# DRV8323.net
KiCad netlist of a schematic drawn in Altium Designer
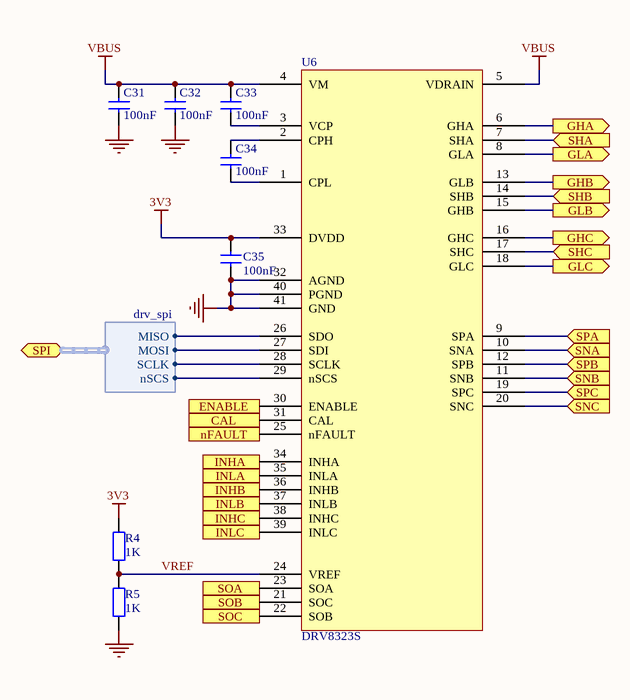
[diagram p0: DRV8323.SchDoc]

(export (version "E")
  (design (tool "Eeschema 10.0.6"))
  (components
    (comp (ref "C31")
      (value "100nF")
      (footprint "CAP0402(1005)_N")
      (description "Capacitor")
      (fields (field (name "PART") "cap_generic"))
      (libsource (lib "hitiqlib") (part "cap"))
    )
    (comp (ref "C32")
      (value "100nF")
      (footprint "CAP0402(1005)_N")
      (description "Capacitor")
      (fields (field (name "PART") "cap_generic"))
      (libsource (lib "hitiqlib") (part "cap"))
    )
    (comp (ref "C33")
      (value "100nF")
      (footprint "CAP0402(1005)_N")
      (description "Capacitor")
      (fields (field (name "PART") "cap_generic"))
      (libsource (lib "hitiqlib") (part "cap"))
    )
    (comp (ref "C34")
      (value "100nF")
      (footprint "CAP0402(1005)_N")
      (description "Capacitor")
      (fields (field (name "PART") "cap_generic"))
      (libsource (lib "hitiqlib") (part "cap"))
    )
    (comp (ref "C35")
      (value "100nF")
      (footprint "CAP0402(1005)_N")
      (description "Capacitor")
      (fields (field (name "PART") "cap_generic"))
      (libsource (lib "hitiqlib") (part "cap"))
    )
    (comp (ref "R4")
      (value "1K")
      (footprint "RESC0402(1005)_N")
      (description "Resistor")
      (fields (field (name "PART") "res_generic"))
      (libsource (lib "hitiqlib") (part "Resistor"))
    )
    (comp (ref "R5")
      (value "1K")
      (footprint "RESC0402(1005)_N")
      (description "Resistor")
      (fields (field (name "PART") "res_generic"))
      (libsource (lib "hitiqlib") (part "Resistor"))
    )
    (comp (ref "U6")
      (value "DRV8323S")
      (footprint "WQFN-40")
      (fields (field (name "MANUFACTURER") "Texas Instruments"))
      (libsource (lib "hitiqlib") (part "DRV8323S"))
    )
  )
  (nets
    (net (code "2") (name "/CAL") (class "Default")
      (node (ref "U6") (pin "31") (pinfunction "CAL_31") (pintype "passive"))
    )
    (net (code "3") (name "/ENABLE") (class "Default")
      (node (ref "U6") (pin "30") (pinfunction "ENABLE_30") (pintype "passive"))
    )
    (net (code "4") (name "/GHA") (class "Default")
      (node (ref "U6") (pin "6") (pinfunction "GHA_6") (pintype "passive"))
    )
    (net (code "5") (name "/GHB") (class "Default")
      (node (ref "U6") (pin "13") (pinfunction "GLB_13") (pintype "passive"))
    )
    (net (code "6") (name "/GHC") (class "Default")
      (node (ref "U6") (pin "16") (pinfunction "GHC_16") (pintype "passive"))
    )
    (net (code "7") (name "/GLA") (class "Default")
      (node (ref "U6") (pin "8") (pinfunction "GLA_8") (pintype "passive"))
    )
    (net (code "8") (name "/GLB") (class "Default")
      (node (ref "U6") (pin "15") (pinfunction "GHB_15") (pintype "passive"))
    )
    (net (code "9") (name "/GLC") (class "Default")
      (node (ref "U6") (pin "18") (pinfunction "GLC_18") (pintype "passive"))
    )
    (net (code "10") (name "/INHA") (class "Default")
      (node (ref "U6") (pin "34") (pinfunction "INHA_34") (pintype "passive"))
    )
    (net (code "11") (name "/INHB") (class "Default")
      (node (ref "U6") (pin "36") (pinfunction "INHB_36") (pintype "passive"))
    )
    (net (code "12") (name "/INHC") (class "Default")
      (node (ref "U6") (pin "38") (pinfunction "INHC_38") (pintype "passive"))
    )
    (net (code "13") (name "/INLA") (class "Default")
      (node (ref "U6") (pin "35") (pinfunction "INLA_35") (pintype "passive"))
    )
    (net (code "14") (name "/INLB") (class "Default")
      (node (ref "U6") (pin "37") (pinfunction "INLB_37") (pintype "passive"))
    )
    (net (code "15") (name "/INLC") (class "Default")
      (node (ref "U6") (pin "39") (pinfunction "INLC_39") (pintype "passive"))
    )
    (net (code "16") (name "/MISO") (class "Default")
      (node (ref "U6") (pin "26") (pinfunction "SDO_26") (pintype "passive"))
    )
    (net (code "17") (name "/MOSI") (class "Default")
      (node (ref "U6") (pin "27") (pinfunction "SDI_27") (pintype "passive"))
    )
    (net (code "18") (name "/SCLK") (class "Default")
      (node (ref "U6") (pin "28") (pinfunction "SCLK_28") (pintype "passive"))
    )
    (net (code "19") (name "/SHA") (class "Default")
      (node (ref "U6") (pin "7") (pinfunction "SHA_7") (pintype "passive"))
    )
    (net (code "20") (name "/SHB") (class "Default")
      (node (ref "U6") (pin "14") (pinfunction "SHB_14") (pintype "passive"))
    )
    (net (code "21") (name "/SHC") (class "Default")
      (node (ref "U6") (pin "17") (pinfunction "SHC_17") (pintype "passive"))
    )
    (net (code "22") (name "/SNA") (class "Default")
      (node (ref "U6") (pin "10") (pinfunction "SNA_10") (pintype "passive"))
    )
    (net (code "23") (name "/SNB") (class "Default")
      (node (ref "U6") (pin "11") (pinfunction "SNB_11") (pintype "passive"))
    )
    (net (code "24") (name "/SNC") (class "Default")
      (node (ref "U6") (pin "20") (pinfunction "SNC_20") (pintype "passive"))
    )
    (net (code "25") (name "/SOA") (class "Default")
      (node (ref "U6") (pin "23") (pinfunction "SOA_23") (pintype "passive"))
    )
    (net (code "26") (name "/SOB") (class "Default")
      (node (ref "U6") (pin "21") (pinfunction "SOC_21") (pintype "passive"))
    )
    (net (code "27") (name "/SOC") (class "Default")
      (node (ref "U6") (pin "22") (pinfunction "SOB_22") (pintype "passive"))
    )
    (net (code "28") (name "/SPA") (class "Default")
      (node (ref "U6") (pin "9") (pinfunction "SPA_9") (pintype "passive"))
    )
    (net (code "29") (name "/SPB") (class "Default")
      (node (ref "U6") (pin "12") (pinfunction "SPB_12") (pintype "passive"))
    )
    (net (code "30") (name "/SPC") (class "Default")
      (node (ref "U6") (pin "19") (pinfunction "SPC_19") (pintype "passive"))
    )
    (net (code "31") (name "/VREF") (class "Default")
      (node (ref "R4") (pin "1") (pintype "passive"))
      (node (ref "R5") (pin "2") (pintype "passive"))
      (node (ref "U6") (pin "24") (pinfunction "VREF_24") (pintype "passive"))
    )
    (net (code "32") (name "/nFAULT") (class "Default")
      (node (ref "U6") (pin "25") (pinfunction "nFAULT_25") (pintype "passive"))
    )
    (net (code "33") (name "/nSCS") (class "Default")
      (node (ref "U6") (pin "29") (pinfunction "nSCS_29") (pintype "passive"))
    )
    (net (code "35") (name "3V3") (class "Default")
      (node (ref "C35") (pin "2") (pintype "passive"))
      (node (ref "R4") (pin "2") (pintype "passive"))
      (node (ref "U6") (pin "33") (pinfunction "DVDD_33") (pintype "passive"))
    )
    (net (code "36") (name "GND") (class "Default")
      (node (ref "C31") (pin "1") (pintype "passive"))
      (node (ref "C32") (pin "1") (pintype "passive"))
      (node (ref "C35") (pin "1") (pintype "passive"))
      (node (ref "R5") (pin "1") (pintype "passive"))
      (node (ref "U6") (pin "32") (pinfunction "AGND_32") (pintype "passive"))
      (node (ref "U6") (pin "40") (pinfunction "PGND_40") (pintype "passive"))
      (node (ref "U6") (pin "41") (pinfunction "GND_41") (pintype "passive"))
    )
    (net (code "37") (name "Net-(U6-CPH)") (class "Default")
      (node (ref "C34") (pin "2") (pintype "passive"))
      (node (ref "U6") (pin "2") (pinfunction "CPH_2") (pintype "passive"))
    )
    (net (code "38") (name "Net-(U6-CPL)") (class "Default")
      (node (ref "C34") (pin "1") (pintype "passive"))
      (node (ref "U6") (pin "1") (pinfunction "CPL_1") (pintype "passive"))
    )
    (net (code "39") (name "Net-(U6-VCP)") (class "Default")
      (node (ref "C33") (pin "1") (pintype "passive"))
      (node (ref "U6") (pin "3") (pinfunction "VCP_3") (pintype "passive"))
    )
    (net (code "40") (name "VBUS") (class "Default")
      (node (ref "C31") (pin "2") (pintype "passive"))
      (node (ref "C32") (pin "2") (pintype "passive"))
      (node (ref "C33") (pin "2") (pintype "passive"))
      (node (ref "U6") (pin "4") (pinfunction "VM_4") (pintype "passive"))
      (node (ref "U6") (pin "5") (pinfunction "VDRAIN_5") (pintype "passive"))
    )
  )
)
